# 2820gpssim.net
KiCad netlist of a schematic drawn in EAGLE
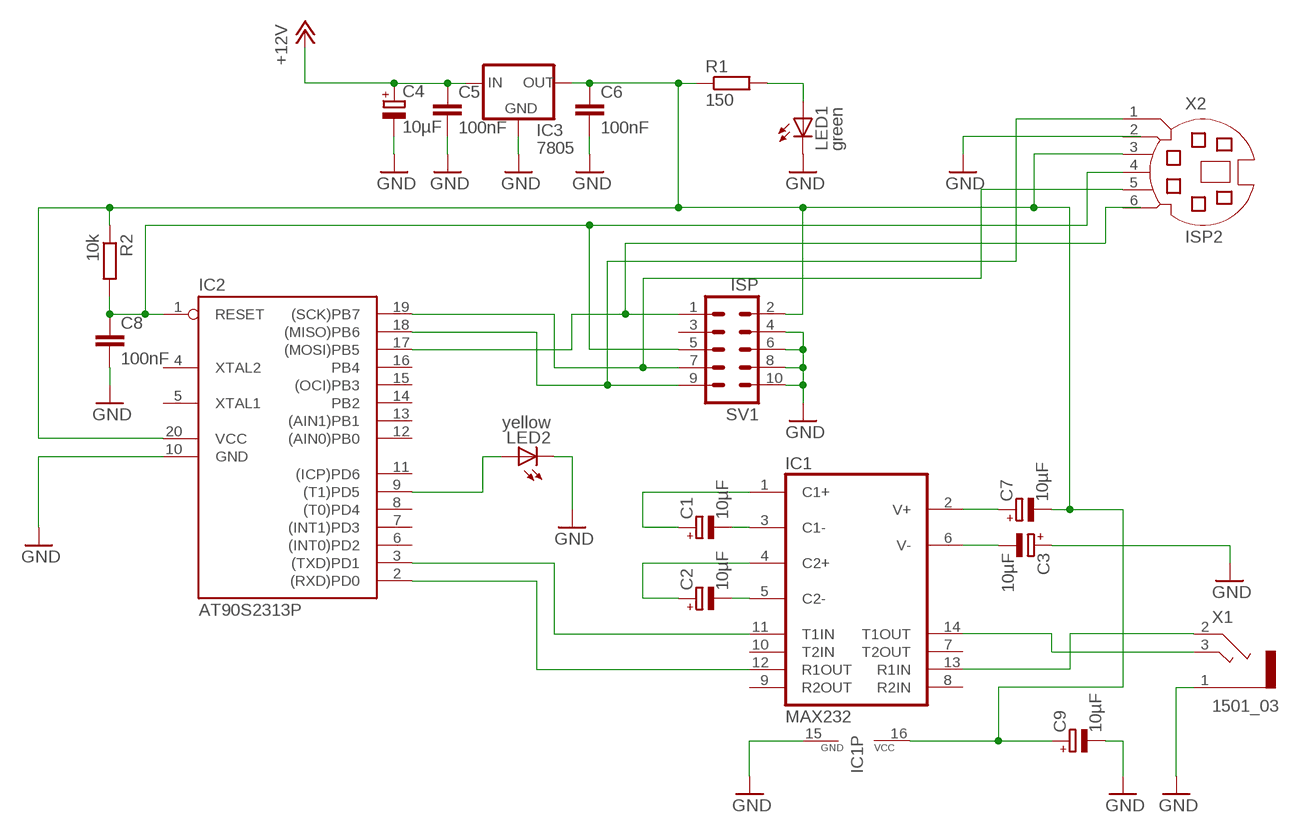
[diagram p0: schematic, sheet 1]

(export (version "E")
  (design (tool "Eeschema 10.0.6"))
  (components
    (comp (ref "C1")
      (value "10µF")
      (footprint "eagle-import:E2,5-5")
      (libsource (lib "eagle-import") (part "CPOL-EUE2.5-5"))
    )
    (comp (ref "C2")
      (value "10µF")
      (footprint "eagle-import:E2,5-5")
      (libsource (lib "eagle-import") (part "CPOL-EUE2.5-5"))
    )
    (comp (ref "C3")
      (value "10µF")
      (footprint "eagle-import:E2,5-5")
      (libsource (lib "eagle-import") (part "CPOL-EUE2.5-5"))
    )
    (comp (ref "C4")
      (value "10µF")
      (footprint "eagle-import:E2,5-5")
      (libsource (lib "eagle-import") (part "CPOL-EUE2.5-5"))
    )
    (comp (ref "C5")
      (value "100nF")
      (footprint "eagle-import:C025-025X050")
      (libsource (lib "eagle-import") (part "C-EU025-025X050"))
    )
    (comp (ref "C6")
      (value "100nF")
      (footprint "eagle-import:C025-025X050")
      (libsource (lib "eagle-import") (part "C-EU025-025X050"))
    )
    (comp (ref "C7")
      (value "10µF")
      (footprint "eagle-import:E2,5-5")
      (libsource (lib "eagle-import") (part "CPOL-EUE2.5-5"))
    )
    (comp (ref "C8")
      (value "100nF")
      (footprint "eagle-import:C025-025X050")
      (libsource (lib "eagle-import") (part "C-EU025-025X050"))
    )
    (comp (ref "C9")
      (value "10µF")
      (footprint "eagle-import:E2,5-5")
      (libsource (lib "eagle-import") (part "CPOL-EUE2.5-5"))
    )
    (comp (ref "IC1")
      (value "MAX232")
      (footprint "eagle-import:DIL16")
      (fields (field (name "MF") "MAXIM") (field (name "MPN") "MAX232ACPE+"))
      (libsource (lib "eagle-import") (part "MAX232"))
    )
    (comp (ref "IC2")
      (value "AT90S2313P")
      (footprint "eagle-import:DIL20")
      (libsource (lib "eagle-import") (part "AT90S2313P"))
    )
    (comp (ref "IC3")
      (value "7805")
      (footprint "eagle-import:78XXL")
      (libsource (lib "eagle-import") (part "78XXL"))
    )
    (comp (ref "LED1")
      (value "green")
      (footprint "eagle-import:LED3MM")
      (libsource (lib "eagle-import") (part "LED3MM"))
    )
    (comp (ref "LED2")
      (value "yellow")
      (footprint "eagle-import:LED3MM")
      (libsource (lib "eagle-import") (part "LED3MM"))
    )
    (comp (ref "R1")
      (value "150")
      (footprint "eagle-import:0204_7")
      (libsource (lib "eagle-import") (part "R-EU_0204/7"))
    )
    (comp (ref "R2")
      (value "10k")
      (footprint "eagle-import:0204_7")
      (libsource (lib "eagle-import") (part "R-EU_0204/7"))
    )
    (comp (ref "SV1")
      (value "ISP")
      (footprint "eagle-import:ML10")
      (libsource (lib "eagle-import") (part "ML10"))
    )
    (comp (ref "X1")
      (value "1501_03")
      (footprint "eagle-import:1501_03")
      (libsource (lib "eagle-import") (part "1501_03"))
    )
    (comp (ref "X2")
      (value "ISP2")
      (footprint "eagle-import:MDIN06SS")
      (libsource (lib "eagle-import") (part "MD06SS"))
    )
  )
  (nets
    (net (code "1") (name "+12V") (class "Default")
      (node (ref "C4") (pin "+") (pinfunction "+_+") (pintype "passive"))
      (node (ref "C5") (pin "1") (pinfunction "1_1") (pintype "passive"))
      (node (ref "IC3") (pin "IN") (pinfunction "IN_IN") (pintype "input"))
    )
    (net (code "2") (name "GND") (class "Default")
      (node (ref "C3") (pin "+") (pinfunction "+_+") (pintype "passive"))
      (node (ref "C4") (pin "-") (pinfunction "-_-") (pintype "passive"))
      (node (ref "C5") (pin "2") (pinfunction "2_2") (pintype "passive"))
      (node (ref "C6") (pin "2") (pinfunction "2_2") (pintype "passive"))
      (node (ref "C8") (pin "2") (pinfunction "2_2") (pintype "passive"))
      (node (ref "C9") (pin "-") (pinfunction "-_-") (pintype "passive"))
      (node (ref "IC1") (pin "15") (pinfunction "GND_15") (pintype "power_in"))
      (node (ref "IC2") (pin "10") (pinfunction "GND_10") (pintype "power_in"))
      (node (ref "IC3") (pin "GND") (pinfunction "GND_GND") (pintype "input"))
      (node (ref "LED1") (pin "K") (pinfunction "C_K") (pintype "passive"))
      (node (ref "LED2") (pin "K") (pinfunction "C_K") (pintype "passive"))
      (node (ref "SV1") (pin "10") (pinfunction "10_10") (pintype "passive"))
      (node (ref "SV1") (pin "4") (pinfunction "4_4") (pintype "passive"))
      (node (ref "SV1") (pin "6") (pinfunction "6_6") (pintype "passive"))
      (node (ref "SV1") (pin "8") (pinfunction "8_8") (pintype "passive"))
      (node (ref "X1") (pin "1") (pinfunction "1_1") (pintype "passive"))
    )
    (net (code "3") (name "Net-(IC1A-C1+)") (class "Default")
      (node (ref "C1") (pin "+") (pinfunction "+_+") (pintype "passive"))
      (node (ref "IC1") (pin "1") (pinfunction "C1+_1") (pintype "bidirectional"))
    )
    (net (code "4") (name "Net-(IC1A-C1-)") (class "Default")
      (node (ref "C1") (pin "-") (pinfunction "-_-") (pintype "passive"))
      (node (ref "IC1") (pin "3") (pinfunction "C1-_3") (pintype "bidirectional"))
    )
    (net (code "5") (name "Net-(IC1A-C2+)") (class "Default")
      (node (ref "C2") (pin "+") (pinfunction "+_+") (pintype "passive"))
      (node (ref "IC1") (pin "4") (pinfunction "C2+_4") (pintype "bidirectional"))
    )
    (net (code "6") (name "Net-(IC1A-C2-)") (class "Default")
      (node (ref "C2") (pin "-") (pinfunction "-_-") (pintype "passive"))
      (node (ref "IC1") (pin "5") (pinfunction "C2-_5") (pintype "bidirectional"))
    )
    (net (code "7") (name "Net-(IC1A-R1IN)") (class "Default")
      (node (ref "IC1") (pin "13") (pinfunction "R1IN_13") (pintype "input"))
      (node (ref "X1") (pin "2") (pinfunction "2_2") (pintype "passive"))
    )
    (net (code "8") (name "Net-(IC1A-R1OUT)") (class "Default")
      (node (ref "IC1") (pin "12") (pinfunction "R1OUT_12") (pintype "output"))
      (node (ref "IC2") (pin "2") (pinfunction "(RXD)PD0_2") (pintype "bidirectional"))
    )
    (net (code "9") (name "Net-(IC1A-T1IN)") (class "Default")
      (node (ref "IC1") (pin "11") (pinfunction "T1IN_11") (pintype "input"))
      (node (ref "IC2") (pin "3") (pinfunction "(TXD)PD1_3") (pintype "bidirectional"))
    )
    (net (code "10") (name "Net-(IC1A-T1OUT)") (class "Default")
      (node (ref "IC1") (pin "14") (pinfunction "T1OUT_14") (pintype "output"))
      (node (ref "X1") (pin "3") (pinfunction "3_3") (pintype "passive"))
    )
    (net (code "11") (name "Net-(IC1A-V+)") (class "Default")
      (node (ref "C7") (pin "+") (pinfunction "+_+") (pintype "passive"))
      (node (ref "IC1") (pin "2") (pinfunction "V+_2") (pintype "bidirectional"))
    )
    (net (code "12") (name "Net-(IC1A-V-)") (class "Default")
      (node (ref "C3") (pin "-") (pinfunction "-_-") (pintype "passive"))
      (node (ref "IC1") (pin "6") (pinfunction "V-_6") (pintype "bidirectional"))
    )
    (net (code "13") (name "Net-(IC1B-VCC)") (class "Default")
      (node (ref "C6") (pin "1") (pinfunction "1_1") (pintype "passive"))
      (node (ref "C7") (pin "-") (pinfunction "-_-") (pintype "passive"))
      (node (ref "C9") (pin "+") (pinfunction "+_+") (pintype "passive"))
      (node (ref "IC1") (pin "16") (pinfunction "VCC_16") (pintype "power_in"))
      (node (ref "IC2") (pin "20") (pinfunction "VCC_20") (pintype "power_in"))
      (node (ref "IC3") (pin "OUT") (pinfunction "OUT_OUT") (pintype "passive"))
      (node (ref "R1") (pin "1") (pinfunction "1_1") (pintype "passive"))
      (node (ref "R2") (pin "1") (pinfunction "1_1") (pintype "passive"))
      (node (ref "SV1") (pin "2") (pinfunction "2_2") (pintype "passive"))
      (node (ref "X2") (pin "3") (pinfunction "3_3") (pintype "passive"))
    )
    (net (code "14") (name "Net-(IC2-(MISO)PB6)") (class "Default")
      (node (ref "IC2") (pin "18") (pinfunction "(MISO)PB6_18") (pintype "bidirectional"))
      (node (ref "SV1") (pin "9") (pinfunction "9_9") (pintype "passive"))
      (node (ref "X2") (pin "1") (pinfunction "1_1") (pintype "passive"))
    )
    (net (code "15") (name "Net-(IC2-(MOSI)PB5)") (class "Default")
      (node (ref "IC2") (pin "17") (pinfunction "(MOSI)PB5_17") (pintype "bidirectional"))
      (node (ref "SV1") (pin "1") (pinfunction "1_1") (pintype "passive"))
    )
    (net (code "16") (name "Net-(IC2-(SCK)PB7)") (class "Default")
      (node (ref "IC2") (pin "19") (pinfunction "(SCK)PB7_19") (pintype "bidirectional"))
      (node (ref "SV1") (pin "7") (pinfunction "7_7") (pintype "passive"))
      (node (ref "X2") (pin "5") (pinfunction "5_5") (pintype "passive"))
    )
    (net (code "17") (name "Net-(IC2-(T1)PD5)") (class "Default")
      (node (ref "IC2") (pin "9") (pinfunction "(T1)PD5_9") (pintype "bidirectional"))
      (node (ref "LED2") (pin "A") (pinfunction "A_A") (pintype "passive"))
    )
    (net (code "18") (name "Net-(IC2-RESET)") (class "Default")
      (node (ref "C8") (pin "1") (pinfunction "1_1") (pintype "passive"))
      (node (ref "IC2") (pin "1") (pinfunction "RESET_1") (pintype "bidirectional"))
      (node (ref "R2") (pin "2") (pinfunction "2_2") (pintype "passive"))
      (node (ref "SV1") (pin "5") (pinfunction "5_5") (pintype "passive"))
      (node (ref "X2") (pin "4") (pinfunction "4_4") (pintype "passive"))
    )
    (net (code "19") (name "Net-(LED1-PadA)") (class "Default")
      (node (ref "LED1") (pin "A") (pinfunction "A_A") (pintype "passive"))
      (node (ref "R1") (pin "2") (pinfunction "2_2") (pintype "passive"))
    )
    (net (code "20") (name "unconnected-(IC1A-R2IN-Pad8)") (class "Default")
      (node (ref "IC1") (pin "8") (pinfunction "R2IN_8") (pintype "input"))
    )
    (net (code "21") (name "unconnected-(IC1A-R2OUT-Pad9)") (class "Default")
      (node (ref "IC1") (pin "9") (pinfunction "R2OUT_9") (pintype "output"))
    )
    (net (code "22") (name "unconnected-(IC1A-T2IN-Pad10)") (class "Default")
      (node (ref "IC1") (pin "10") (pinfunction "T2IN_10") (pintype "input"))
    )
    (net (code "23") (name "unconnected-(IC1A-T2OUT-Pad7)") (class "Default")
      (node (ref "IC1") (pin "7") (pinfunction "T2OUT_7") (pintype "output"))
    )
    (net (code "24") (name "unconnected-(IC2-(AIN0)PB0-Pad12)") (class "Default")
      (node (ref "IC2") (pin "12") (pinfunction "(AIN0)PB0_12") (pintype "bidirectional"))
    )
    (net (code "25") (name "unconnected-(IC2-(AIN1)PB1-Pad13)") (class "Default")
      (node (ref "IC2") (pin "13") (pinfunction "(AIN1)PB1_13") (pintype "bidirectional"))
    )
    (net (code "26") (name "unconnected-(IC2-(ICP)PD6-Pad11)") (class "Default")
      (node (ref "IC2") (pin "11") (pinfunction "(ICP)PD6_11") (pintype "bidirectional"))
    )
    (net (code "27") (name "unconnected-(IC2-(INT0)PD2-Pad6)") (class "Default")
      (node (ref "IC2") (pin "6") (pinfunction "(INT0)PD2_6") (pintype "bidirectional"))
    )
    (net (code "28") (name "unconnected-(IC2-(INT1)PD3-Pad7)") (class "Default")
      (node (ref "IC2") (pin "7") (pinfunction "(INT1)PD3_7") (pintype "bidirectional"))
    )
    (net (code "29") (name "unconnected-(IC2-(OCI)PB3-Pad15)") (class "Default")
      (node (ref "IC2") (pin "15") (pinfunction "(OCI)PB3_15") (pintype "bidirectional"))
    )
    (net (code "30") (name "unconnected-(IC2-(T0)PD4-Pad8)") (class "Default")
      (node (ref "IC2") (pin "8") (pinfunction "(T0)PD4_8") (pintype "bidirectional"))
    )
    (net (code "31") (name "unconnected-(IC2-PB2-Pad14)") (class "Default")
      (node (ref "IC2") (pin "14") (pinfunction "PB2_14") (pintype "bidirectional"))
    )
    (net (code "32") (name "unconnected-(IC2-PB4-Pad16)") (class "Default")
      (node (ref "IC2") (pin "16") (pinfunction "PB4_16") (pintype "bidirectional"))
    )
    (net (code "33") (name "unconnected-(IC2-XTAL1-Pad5)") (class "Default")
      (node (ref "IC2") (pin "5") (pinfunction "XTAL1_5") (pintype "bidirectional"))
    )
    (net (code "34") (name "unconnected-(IC2-XTAL2-Pad4)") (class "Default")
      (node (ref "IC2") (pin "4") (pinfunction "XTAL2_4") (pintype "bidirectional"))
    )
    (net (code "35") (name "unconnected-(SV1-Pad3)") (class "Default")
      (node (ref "SV1") (pin "3") (pinfunction "3_3") (pintype "passive"))
    )
    (net (code "36") (name "unconnected-(X2-Pad2)") (class "Default")
      (node (ref "X2") (pin "2") (pinfunction "2_2") (pintype "passive"))
    )
    (net (code "37") (name "unconnected-(X2-Pad6)") (class "Default")
      (node (ref "X2") (pin "6") (pinfunction "6_6") (pintype "passive"))
    )
  )
)
